# LPC2368_Breakout.net
KiCad netlist of a schematic drawn in EAGLE
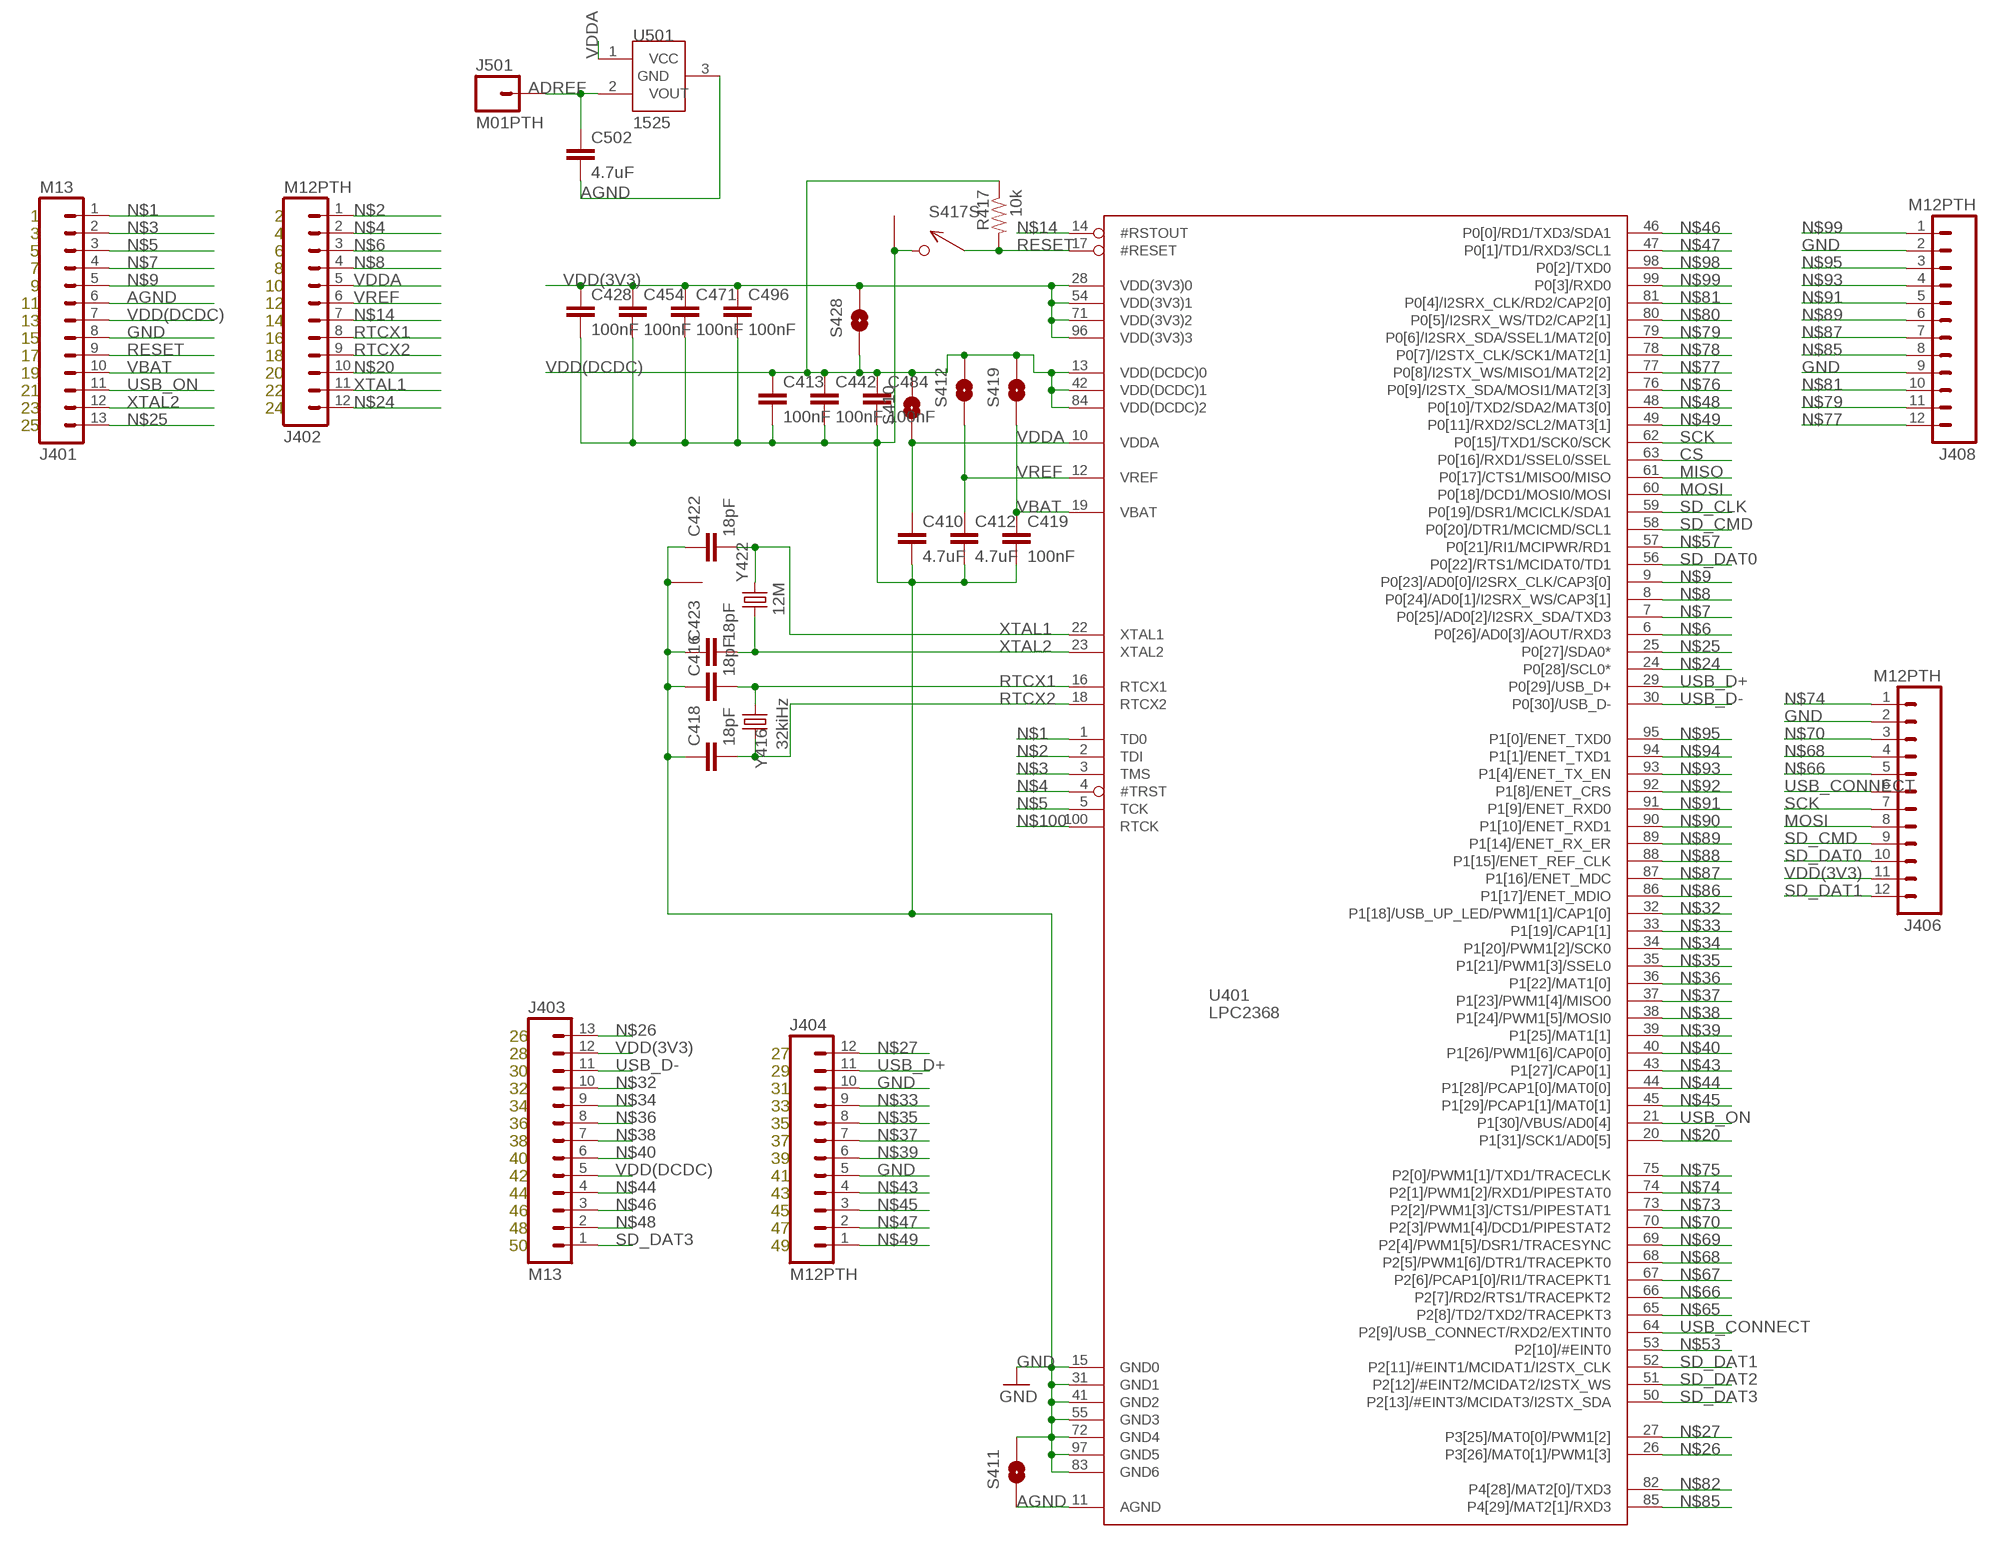
[diagram p0: schematic, sheet 1, part 1 of 2]
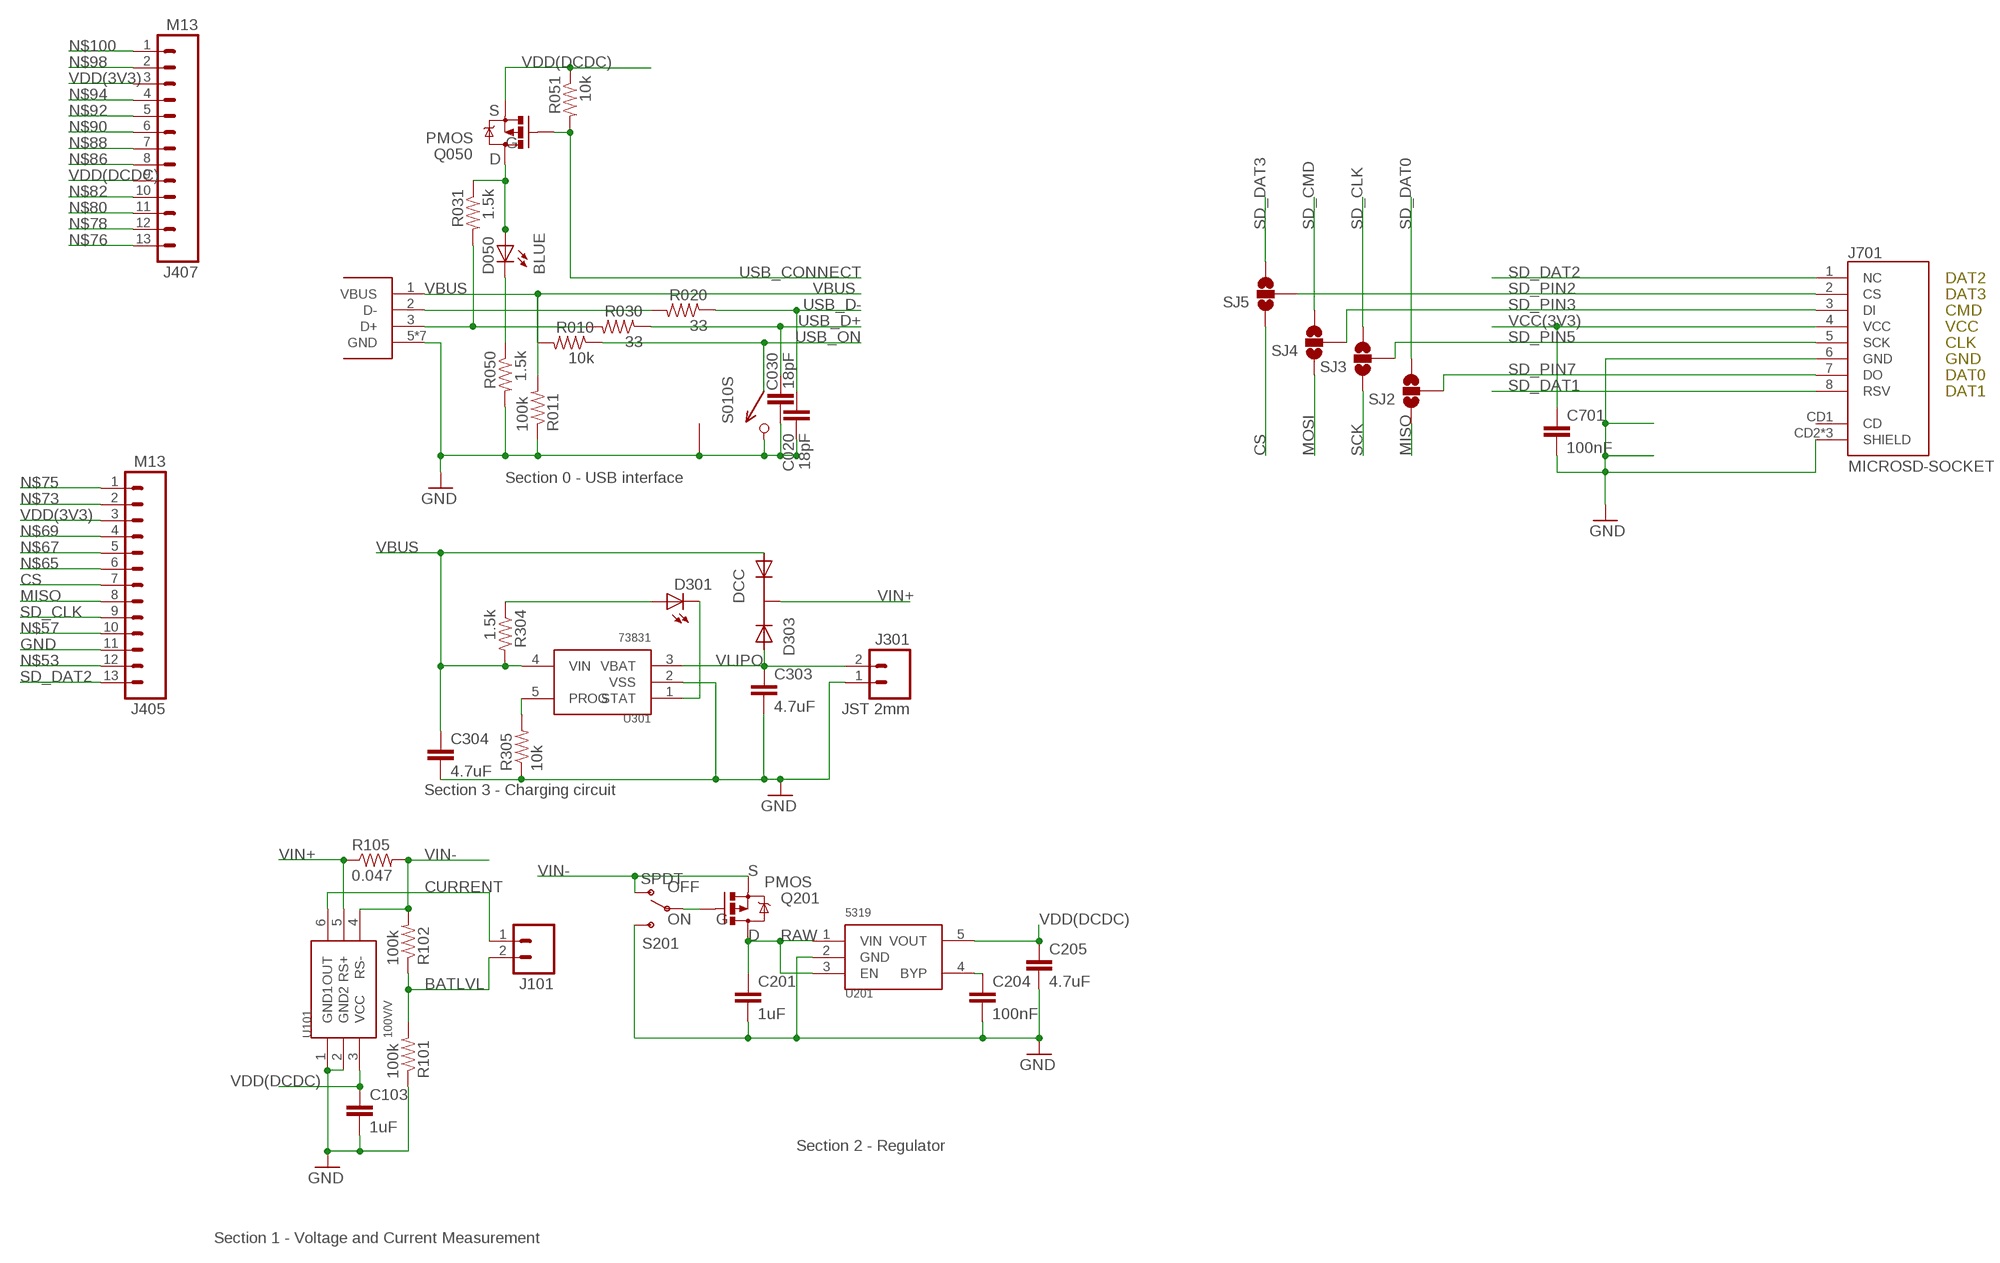
[diagram p1: schematic, sheet 1, part 2 of 2]

(export (version "E")
  (design (tool "Eeschema 10.0.6"))
  (components
    (comp (ref "C020")
      (value "18pF")
      (footprint "eagle-import:0402-CAP")
      (libsource (lib "eagle-import") (part "CAP0402-CAP"))
    )
    (comp (ref "C030")
      (value "18pF")
      (footprint "eagle-import:0402-CAP")
      (libsource (lib "eagle-import") (part "CAP0402-CAP"))
    )
    (comp (ref "C103")
      (value "1uF")
      (footprint "eagle-import:0402-CAP")
      (libsource (lib "eagle-import") (part "CAP0402-CAP"))
    )
    (comp (ref "C201")
      (value "1uF")
      (footprint "eagle-import:0402-CAP")
      (libsource (lib "eagle-import") (part "CAP0402-CAP"))
    )
    (comp (ref "C204")
      (value "100nF")
      (footprint "eagle-import:0402-CAP")
      (libsource (lib "eagle-import") (part "CAP0402-CAP"))
    )
    (comp (ref "C205")
      (value "4.7uF")
      (footprint "eagle-import:0402-CAP")
      (libsource (lib "eagle-import") (part "CAP0402-CAP"))
    )
    (comp (ref "C303")
      (value "4.7uF")
      (footprint "eagle-import:0402-CAP")
      (libsource (lib "eagle-import") (part "CAP0402-CAP"))
    )
    (comp (ref "C304")
      (value "4.7uF")
      (footprint "eagle-import:0402-CAP")
      (libsource (lib "eagle-import") (part "CAP0402-CAP"))
    )
    (comp (ref "C410")
      (value "4.7uF")
      (footprint "eagle-import:0402-CAP")
      (libsource (lib "eagle-import") (part "SparkFun-Passives_CAP0402-CAP"))
    )
    (comp (ref "C412")
      (value "4.7uF")
      (footprint "eagle-import:0402-CAP")
      (libsource (lib "eagle-import") (part "SparkFun-Passives_CAP0402-CAP"))
    )
    (comp (ref "C413")
      (value "100nF")
      (footprint "eagle-import:0402-CAP")
      (libsource (lib "eagle-import") (part "SparkFun-Passives_CAP0402-CAP"))
    )
    (comp (ref "C416")
      (value "18pF")
      (footprint "eagle-import:0402-CAP")
      (libsource (lib "eagle-import") (part "SparkFun-Passives_CAP0402-CAP"))
    )
    (comp (ref "C418")
      (value "18pF")
      (footprint "eagle-import:0402-CAP")
      (libsource (lib "eagle-import") (part "SparkFun-Passives_CAP0402-CAP"))
    )
    (comp (ref "C419")
      (value "100nF")
      (footprint "eagle-import:0402-CAP")
      (libsource (lib "eagle-import") (part "SparkFun-Passives_CAP0402-CAP"))
    )
    (comp (ref "C422")
      (value "18pF")
      (footprint "eagle-import:0402-CAP")
      (libsource (lib "eagle-import") (part "SparkFun-Passives_CAP0402-CAP"))
    )
    (comp (ref "C423")
      (value "18pF")
      (footprint "eagle-import:0402-CAP")
      (libsource (lib "eagle-import") (part "SparkFun-Passives_CAP0402-CAP"))
    )
    (comp (ref "C428")
      (value "100nF")
      (footprint "eagle-import:0402-CAP")
      (libsource (lib "eagle-import") (part "SparkFun-Passives_CAP0402-CAP"))
    )
    (comp (ref "C442")
      (value "100nF")
      (footprint "eagle-import:0402-CAP")
      (libsource (lib "eagle-import") (part "SparkFun-Passives_CAP0402-CAP"))
    )
    (comp (ref "C454")
      (value "100nF")
      (footprint "eagle-import:0402-CAP")
      (libsource (lib "eagle-import") (part "SparkFun-Passives_CAP0402-CAP"))
    )
    (comp (ref "C471")
      (value "100nF")
      (footprint "eagle-import:0402-CAP")
      (libsource (lib "eagle-import") (part "SparkFun-Passives_CAP0402-CAP"))
    )
    (comp (ref "C484")
      (value "100nF")
      (footprint "eagle-import:0402-CAP")
      (libsource (lib "eagle-import") (part "SparkFun-Passives_CAP0402-CAP"))
    )
    (comp (ref "C496")
      (value "100nF")
      (footprint "eagle-import:0402-CAP")
      (libsource (lib "eagle-import") (part "SparkFun-Passives_CAP0402-CAP"))
    )
    (comp (ref "C502")
      (value "4.7uF")
      (footprint "eagle-import:0402-CAP")
      (libsource (lib "eagle-import") (part "CAP0402-CAP"))
    )
    (comp (ref "C701")
      (value "100nF")
      (footprint "eagle-import:0402-CAP")
      (libsource (lib "eagle-import") (part "CAP0402-CAP"))
    )
    (comp (ref "D050")
      (value "BLUE")
      (footprint "eagle-import:LED-0603")
      (libsource (lib "eagle-import") (part "LED0603"))
    )
    (comp (ref "D301")
      (value "YELLOW")
      (footprint "eagle-import:LED-0603")
      (libsource (lib "eagle-import") (part "LED0603"))
    )
    (comp (ref "D303")
      (value "DCC")
      (footprint "eagle-import:SOT-23-3")
      (libsource (lib "eagle-import") (part "PMEG2005CT"))
    )
    (comp (ref "J001")
      (value "USB_MICROB_JST")
      (footprint "eagle-import:UB-MC5BR3-SD204-4S")
      (libsource (lib "eagle-import") (part "USB_MICROB_JST"))
    )
    (comp (ref "J101")
      (value "M02PTH")
      (footprint "eagle-import:1X02")
      (libsource (lib "eagle-import") (part "SparkFun-Connectors_M02PTH"))
    )
    (comp (ref "J301")
      (value "JST 2mm")
      (footprint "eagle-import:JST-2-SMD")
      (libsource (lib "eagle-import") (part "M02-JST-2MM-SMT"))
    )
    (comp (ref "J401")
      (value "M13")
      (footprint "eagle-import:1X13")
      (libsource (lib "eagle-import") (part "M13"))
    )
    (comp (ref "J402")
      (value "M12PTH")
      (footprint "eagle-import:1X12")
      (libsource (lib "eagle-import") (part "M12PTH"))
    )
    (comp (ref "J403")
      (value "M13")
      (footprint "eagle-import:1X13")
      (libsource (lib "eagle-import") (part "M13"))
    )
    (comp (ref "J404")
      (value "M12PTH")
      (footprint "eagle-import:1X12")
      (libsource (lib "eagle-import") (part "M12PTH"))
    )
    (comp (ref "J405")
      (value "M13")
      (footprint "eagle-import:1X13")
      (libsource (lib "eagle-import") (part "M13"))
    )
    (comp (ref "J406")
      (value "M12PTH")
      (footprint "eagle-import:1X12")
      (libsource (lib "eagle-import") (part "M12PTH"))
    )
    (comp (ref "J407")
      (value "M13")
      (footprint "eagle-import:1X13")
      (libsource (lib "eagle-import") (part "M13"))
    )
    (comp (ref "J408")
      (value "M12PTH")
      (footprint "eagle-import:1X12")
      (libsource (lib "eagle-import") (part "M12PTH"))
    )
    (comp (ref "J501")
      (value "M01PTH")
      (footprint "eagle-import:1X01")
      (libsource (lib "eagle-import") (part "M01PTH"))
    )
    (comp (ref "J701")
      (value "MICROSD-SOCKET")
      (footprint "eagle-import:MICROSD-SOCKET-PP")
      (libsource (lib "eagle-import") (part "MICROSD-SOCKET"))
    )
    (comp (ref "Q050")
      (value "PMOS")
      (footprint "eagle-import:SOT23-3")
      (libsource (lib "eagle-import") (part "MOSFET-PCHANNELSMD"))
    )
    (comp (ref "Q201")
      (value "PMOS")
      (footprint "eagle-import:SOT23-3")
      (libsource (lib "eagle-import") (part "MOSFET-PCHANNELSMD"))
    )
    (comp (ref "R010")
      (value "10k")
      (footprint "eagle-import:0402-RES")
      (libsource (lib "eagle-import") (part "RESISTOR0402-RES"))
    )
    (comp (ref "R011")
      (value "100k")
      (footprint "eagle-import:0402-RES")
      (libsource (lib "eagle-import") (part "RESISTOR0402-RES"))
    )
    (comp (ref "R020")
      (value "33")
      (footprint "eagle-import:0402-RES")
      (libsource (lib "eagle-import") (part "RESISTOR0402-RES"))
    )
    (comp (ref "R030")
      (value "33")
      (footprint "eagle-import:0402-RES")
      (libsource (lib "eagle-import") (part "RESISTOR0402-RES"))
    )
    (comp (ref "R031")
      (value "1.5k")
      (footprint "eagle-import:0402-RES")
      (libsource (lib "eagle-import") (part "RESISTOR0402-RES"))
    )
    (comp (ref "R050")
      (value "1.5k")
      (footprint "eagle-import:0402-RES")
      (libsource (lib "eagle-import") (part "RESISTOR0402-RES"))
    )
    (comp (ref "R051")
      (value "10k")
      (footprint "eagle-import:0402-RES")
      (libsource (lib "eagle-import") (part "RESISTOR0402-RES"))
    )
    (comp (ref "R101")
      (value "100k")
      (footprint "eagle-import:0402-RES")
      (libsource (lib "eagle-import") (part "RESISTOR0402-RES"))
    )
    (comp (ref "R102")
      (value "100k")
      (footprint "eagle-import:0402-RES")
      (libsource (lib "eagle-import") (part "RESISTOR0402-RES"))
    )
    (comp (ref "R105")
      (value "0.047")
      (footprint "eagle-import:0402-RES")
      (libsource (lib "eagle-import") (part "RESISTOR0402-RES"))
    )
    (comp (ref "R304")
      (value "1.5k")
      (footprint "eagle-import:0402-RES")
      (libsource (lib "eagle-import") (part "RESISTOR0402-RES"))
    )
    (comp (ref "R305")
      (value "10k")
      (footprint "eagle-import:0402-RES")
      (libsource (lib "eagle-import") (part "RESISTOR0402-RES"))
    )
    (comp (ref "R417")
      (value "10k")
      (footprint "eagle-import:0402-RES")
      (libsource (lib "eagle-import") (part "RESISTOR0402-RES"))
    )
    (comp (ref "S010")
      (value "SPST")
      (footprint "eagle-import:B3U-1100P")
      (fields (field (name "DIGIKEY") "SW1021CT-ND"))
      (libsource (lib "eagle-import") (part "B3U-1100P"))
    )
    (comp (ref "S201")
      (value "SPDT")
      (footprint "eagle-import:AYZ0202")
      (libsource (lib "eagle-import") (part "SWITCH-SPSTSMD"))
    )
    (comp (ref "S410")
      (value "SOLDERJUMPERNO")
      (footprint "eagle-import:SJ_2S-NO")
      (libsource (lib "eagle-import") (part "SOLDERJUMPERNO"))
    )
    (comp (ref "S411")
      (value "SOLDERJUMPERNO")
      (footprint "eagle-import:SJ_2S-NO")
      (libsource (lib "eagle-import") (part "SOLDERJUMPERNO"))
    )
    (comp (ref "S412")
      (value "SOLDERJUMPERNO")
      (footprint "eagle-import:SJ_2S-NO")
      (libsource (lib "eagle-import") (part "SOLDERJUMPERNO"))
    )
    (comp (ref "S417")
      (value "SPST")
      (footprint "eagle-import:B3U-1100P")
      (fields (field (name "DIGIKEY") "SW1021CT-ND"))
      (libsource (lib "eagle-import") (part "B3U-1100P"))
    )
    (comp (ref "S419")
      (value "SOLDERJUMPERNO")
      (footprint "eagle-import:SJ_2S-NO")
      (libsource (lib "eagle-import") (part "SOLDERJUMPERNO"))
    )
    (comp (ref "S428")
      (value "SOLDERJUMPERNO")
      (footprint "eagle-import:SJ_2S-NO")
      (libsource (lib "eagle-import") (part "SOLDERJUMPERNO"))
    )
    (comp (ref "SJ2")
      (value "SOLDERJUMPER_2WAYS")
      (footprint "eagle-import:SJ_3")
      (libsource (lib "eagle-import") (part "SOLDERJUMPER_2WAYS"))
    )
    (comp (ref "SJ3")
      (value "SOLDERJUMPER_2WAYS")
      (footprint "eagle-import:SJ_3")
      (libsource (lib "eagle-import") (part "SOLDERJUMPER_2WAYS"))
    )
    (comp (ref "SJ4")
      (value "SOLDERJUMPER_2WAYS")
      (footprint "eagle-import:SJ_3")
      (libsource (lib "eagle-import") (part "SOLDERJUMPER_2WAYS"))
    )
    (comp (ref "SJ5")
      (value "SOLDERJUMPER_2WAYS")
      (footprint "eagle-import:SJ_3")
      (libsource (lib "eagle-import") (part "SOLDERJUMPER_2WAYS"))
    )
    (comp (ref "U101")
      (value "100V/V")
      (footprint "eagle-import:SOT-23-6")
      (libsource (lib "eagle-import") (part "MAX4173"))
    )
    (comp (ref "U201")
      (value "5319")
      (footprint "eagle-import:SOT-23-5")
      (libsource (lib "eagle-import") (part "MIC5319D5"))
    )
    (comp (ref "U301")
      (value "73831")
      (footprint "eagle-import:SOT-23-5")
      (libsource (lib "eagle-import") (part "MCP73831"))
    )
    (comp (ref "U401")
      (value "LPC2368")
      (footprint "eagle-import:LQFP100")
      (libsource (lib "eagle-import") (part "LPC2368"))
    )
    (comp (ref "U501")
      (value "1525")
      (footprint "eagle-import:SOT-23-3")
      (libsource (lib "eagle-import") (part "MCP1525"))
    )
    (comp (ref "Y416")
      (value "32kiHz")
      (footprint "eagle-import:CRYSTAL-32KHZ-SMD")
      (libsource (lib "eagle-import") (part "CRYSTAL32-SMD"))
    )
    (comp (ref "Y422")
      (value "12M")
      (footprint "eagle-import:CRYSTAL_SMD")
      (fields (field (name "DIGIKEY") "887-1316-1-ND"))
      (libsource (lib "eagle-import") (part "TSX-3225"))
    )
  )
  (nets
    (net (code "1") (name "/ADREF") (class "Default")
      (node (ref "C502") (pin "1") (pinfunction "1_1") (pintype "passive"))
      (node (ref "J501") (pin "1") (pinfunction "1_1") (pintype "passive"))
      (node (ref "U501") (pin "2") (pinfunction "VOUT_2") (pintype "bidirectional"))
    )
    (net (code "2") (name "/AGND") (class "Default")
      (node (ref "C502") (pin "2") (pinfunction "2_2") (pintype "passive"))
      (node (ref "J401") (pin "6") (pinfunction "6_6") (pintype "passive"))
      (node (ref "S411") (pin "1") (pinfunction "1_1") (pintype "passive"))
      (node (ref "U401") (pin "11") (pinfunction "AGND_11") (pintype "bidirectional"))
      (node (ref "U501") (pin "3") (pinfunction "GND_3") (pintype "bidirectional"))
    )
    (net (code "3") (name "/BATLVL") (class "Default")
      (node (ref "J101") (pin "2") (pinfunction "2_2") (pintype "passive"))
      (node (ref "R101") (pin "2") (pinfunction "2_2") (pintype "passive"))
      (node (ref "R102") (pin "1") (pinfunction "1_1") (pintype "passive"))
    )
    (net (code "4") (name "/CS") (class "Default")
      (node (ref "J405") (pin "7") (pinfunction "7_7") (pintype "passive"))
      (node (ref "SJ5") (pin "1") (pinfunction "1_1") (pintype "passive"))
      (node (ref "U401") (pin "63") (pinfunction "P0[16]/RXD1/SSEL0/SSEL_63") (pintype "bidirectional"))
    )
    (net (code "5") (name "/CURRENT") (class "Default")
      (node (ref "J101") (pin "1") (pinfunction "1_1") (pintype "passive"))
      (node (ref "U101") (pin "6") (pinfunction "OUT_6") (pintype "bidirectional"))
    )
    (net (code "6") (name "/MISO") (class "Default")
      (node (ref "J405") (pin "8") (pinfunction "8_8") (pintype "passive"))
      (node (ref "SJ2") (pin "1") (pinfunction "1_1") (pintype "passive"))
      (node (ref "U401") (pin "61") (pinfunction "P0[17]/CTS1/MISO0/MISO_61") (pintype "bidirectional"))
    )
    (net (code "7") (name "/MOSI") (class "Default")
      (node (ref "J406") (pin "8") (pinfunction "8_8") (pintype "passive"))
      (node (ref "SJ4") (pin "1") (pinfunction "1_1") (pintype "passive"))
      (node (ref "U401") (pin "60") (pinfunction "P0[18]/DCD1/MOSI0/MOSI_60") (pintype "bidirectional"))
    )
    (net (code "8") (name "/N$1") (class "Default")
      (node (ref "J401") (pin "1") (pinfunction "1_1") (pintype "passive"))
      (node (ref "U401") (pin "1") (pinfunction "TD0_1") (pintype "bidirectional"))
    )
    (net (code "9") (name "/N$2") (class "Default")
      (node (ref "J402") (pin "1") (pinfunction "1_1") (pintype "passive"))
      (node (ref "U401") (pin "2") (pinfunction "TDI_2") (pintype "bidirectional"))
    )
    (net (code "10") (name "/N$3") (class "Default")
      (node (ref "J401") (pin "2") (pinfunction "2_2") (pintype "passive"))
      (node (ref "U401") (pin "3") (pinfunction "TMS_3") (pintype "bidirectional"))
    )
    (net (code "11") (name "/N$4") (class "Default")
      (node (ref "J402") (pin "2") (pinfunction "2_2") (pintype "passive"))
      (node (ref "U401") (pin "4") (pinfunction "#TRST_4") (pintype "bidirectional"))
    )
    (net (code "12") (name "/N$5") (class "Default")
      (node (ref "J401") (pin "3") (pinfunction "3_3") (pintype "passive"))
      (node (ref "U401") (pin "5") (pinfunction "TCK_5") (pintype "bidirectional"))
    )
    (net (code "13") (name "/N$6") (class "Default")
      (node (ref "J402") (pin "3") (pinfunction "3_3") (pintype "passive"))
      (node (ref "U401") (pin "6") (pinfunction "P0[26]/AD0[3]/AOUT/RXD3_6") (pintype "bidirectional"))
    )
    (net (code "14") (name "/N$7") (class "Default")
      (node (ref "J401") (pin "4") (pinfunction "4_4") (pintype "passive"))
      (node (ref "U401") (pin "7") (pinfunction "P0[25]/AD0[2]/I2SRX_SDA/TXD3_7") (pintype "bidirectional"))
    )
    (net (code "15") (name "/N$8") (class "Default")
      (node (ref "J402") (pin "4") (pinfunction "4_4") (pintype "passive"))
      (node (ref "U401") (pin "8") (pinfunction "P0[24]/AD0[1]/I2SRX_WS/CAP3[1]_8") (pintype "bidirectional"))
    )
    (net (code "16") (name "/N$9") (class "Default")
      (node (ref "J401") (pin "5") (pinfunction "5_5") (pintype "passive"))
      (node (ref "U401") (pin "9") (pinfunction "P0[23]/AD0[0]/I2SRX_CLK/CAP3[0]_9") (pintype "bidirectional"))
    )
    (net (code "17") (name "/N$14") (class "Default")
      (node (ref "J402") (pin "7") (pinfunction "7_7") (pintype "passive"))
      (node (ref "U401") (pin "14") (pinfunction "#RSTOUT_14") (pintype "bidirectional"))
    )
    (net (code "18") (name "/N$20") (class "Default")
      (node (ref "J402") (pin "10") (pinfunction "10_10") (pintype "passive"))
      (node (ref "U401") (pin "20") (pinfunction "P1[31]/SCK1/AD0[5]_20") (pintype "bidirectional"))
    )
    (net (code "19") (name "/N$24") (class "Default")
      (node (ref "J402") (pin "12") (pinfunction "12_12") (pintype "passive"))
      (node (ref "U401") (pin "24") (pinfunction "P0[28]/SCL0*_24") (pintype "bidirectional"))
    )
    (net (code "20") (name "/N$25") (class "Default")
      (node (ref "J401") (pin "13") (pinfunction "13_13") (pintype "passive"))
      (node (ref "U401") (pin "25") (pinfunction "P0[27]/SDA0*_25") (pintype "bidirectional"))
    )
    (net (code "21") (name "/N$26") (class "Default")
      (node (ref "J403") (pin "13") (pinfunction "13_13") (pintype "passive"))
      (node (ref "U401") (pin "26") (pinfunction "P3[26]/MAT0[1]/PWM1[3]_26") (pintype "bidirectional"))
    )
    (net (code "22") (name "/N$27") (class "Default")
      (node (ref "J404") (pin "12") (pinfunction "12_12") (pintype "passive"))
      (node (ref "U401") (pin "27") (pinfunction "P3[25]/MAT0[0]/PWM1[2]_27") (pintype "bidirectional"))
    )
    (net (code "23") (name "/N$32") (class "Default")
      (node (ref "J403") (pin "10") (pinfunction "10_10") (pintype "passive"))
      (node (ref "U401") (pin "32") (pinfunction "P1[18]/USB_UP_LED/PWM1[1]/CAP1[0]_32") (pintype "bidirectional"))
    )
    (net (code "24") (name "/N$33") (class "Default")
      (node (ref "J404") (pin "9") (pinfunction "9_9") (pintype "passive"))
      (node (ref "U401") (pin "33") (pinfunction "P1[19]/CAP1[1]_33") (pintype "bidirectional"))
    )
    (net (code "25") (name "/N$34") (class "Default")
      (node (ref "J403") (pin "9") (pinfunction "9_9") (pintype "passive"))
      (node (ref "U401") (pin "34") (pinfunction "P1[20]/PWM1[2]/SCK0_34") (pintype "bidirectional"))
    )
    (net (code "26") (name "/N$35") (class "Default")
      (node (ref "J404") (pin "8") (pinfunction "8_8") (pintype "passive"))
      (node (ref "U401") (pin "35") (pinfunction "P1[21]/PWM1[3]/SSEL0_35") (pintype "bidirectional"))
    )
    (net (code "27") (name "/N$36") (class "Default")
      (node (ref "J403") (pin "8") (pinfunction "8_8") (pintype "passive"))
      (node (ref "U401") (pin "36") (pinfunction "P1[22]/MAT1[0]_36") (pintype "bidirectional"))
    )
    (net (code "28") (name "/N$37") (class "Default")
      (node (ref "J404") (pin "7") (pinfunction "7_7") (pintype "passive"))
      (node (ref "U401") (pin "37") (pinfunction "P1[23]/PWM1[4]/MISO0_37") (pintype "bidirectional"))
    )
    (net (code "29") (name "/N$38") (class "Default")
      (node (ref "J403") (pin "7") (pinfunction "7_7") (pintype "passive"))
      (node (ref "U401") (pin "38") (pinfunction "P1[24]/PWM1[5]/MOSI0_38") (pintype "bidirectional"))
    )
    (net (code "30") (name "/N$39") (class "Default")
      (node (ref "J404") (pin "6") (pinfunction "6_6") (pintype "passive"))
      (node (ref "U401") (pin "39") (pinfunction "P1[25]/MAT1[1]_39") (pintype "bidirectional"))
    )
    (net (code "31") (name "/N$40") (class "Default")
      (node (ref "J403") (pin "6") (pinfunction "6_6") (pintype "passive"))
      (node (ref "U401") (pin "40") (pinfunction "P1[26]/PWM1[6]/CAP0[0]_40") (pintype "bidirectional"))
    )
    (net (code "32") (name "/N$43") (class "Default")
      (node (ref "J404") (pin "4") (pinfunction "4_4") (pintype "passive"))
      (node (ref "U401") (pin "43") (pinfunction "P1[27]/CAP0[1]_43") (pintype "bidirectional"))
    )
    (net (code "33") (name "/N$44") (class "Default")
      (node (ref "J403") (pin "4") (pinfunction "4_4") (pintype "passive"))
      (node (ref "U401") (pin "44") (pinfunction "P1[28]/PCAP1[0]/MAT0[0]_44") (pintype "bidirectional"))
    )
    (net (code "34") (name "/N$45") (class "Default")
      (node (ref "J404") (pin "3") (pinfunction "3_3") (pintype "passive"))
      (node (ref "U401") (pin "45") (pinfunction "P1[29]/PCAP1[1]/MAT0[1]_45") (pintype "bidirectional"))
    )
    (net (code "35") (name "/N$46") (class "Default")
      (node (ref "J403") (pin "3") (pinfunction "3_3") (pintype "passive"))
      (node (ref "U401") (pin "46") (pinfunction "P0[0]/RD1/TXD3/SDA1_46") (pintype "bidirectional"))
    )
    (net (code "36") (name "/N$47") (class "Default")
      (node (ref "J404") (pin "2") (pinfunction "2_2") (pintype "passive"))
      (node (ref "U401") (pin "47") (pinfunction "P0[1]/TD1/RXD3/SCL1_47") (pintype "bidirectional"))
    )
    (net (code "37") (name "/N$48") (class "Default")
      (node (ref "J403") (pin "2") (pinfunction "2_2") (pintype "passive"))
      (node (ref "U401") (pin "48") (pinfunction "P0[10]/TXD2/SDA2/MAT3[0]_48") (pintype "bidirectional"))
    )
    (net (code "38") (name "/N$49") (class "Default")
      (node (ref "J404") (pin "1") (pinfunction "1_1") (pintype "passive"))
      (node (ref "U401") (pin "49") (pinfunction "P0[11]/RXD2/SCL2/MAT3[1]_49") (pintype "bidirectional"))
    )
    (net (code "39") (name "/N$53") (class "Default")
      (node (ref "J405") (pin "12") (pinfunction "12_12") (pintype "passive"))
      (node (ref "U401") (pin "53") (pinfunction "P2[10]/#EINT0_53") (pintype "bidirectional"))
    )
    (net (code "40") (name "/N$57") (class "Default")
      (node (ref "J405") (pin "10") (pinfunction "10_10") (pintype "passive"))
      (node (ref "U401") (pin "57") (pinfunction "P0[21]/RI1/MCIPWR/RD1_57") (pintype "bidirectional"))
    )
    (net (code "41") (name "/N$65") (class "Default")
      (node (ref "J405") (pin "6") (pinfunction "6_6") (pintype "passive"))
      (node (ref "U401") (pin "65") (pinfunction "P2[8]/TD2/TXD2/TRACEPKT3_65") (pintype "bidirectional"))
    )
    (net (code "42") (name "/N$66") (class "Default")
      (node (ref "J406") (pin "5") (pinfunction "5_5") (pintype "passive"))
      (node (ref "U401") (pin "66") (pinfunction "P2[7]/RD2/RTS1/TRACEPKT2_66") (pintype "bidirectional"))
    )
    (net (code "43") (name "/N$67") (class "Default")
      (node (ref "J405") (pin "5") (pinfunction "5_5") (pintype "passive"))
      (node (ref "U401") (pin "67") (pinfunction "P2[6]/PCAP1[0]/RI1/TRACEPKT1_67") (pintype "bidirectional"))
    )
    (net (code "44") (name "/N$68") (class "Default")
      (node (ref "J406") (pin "4") (pinfunction "4_4") (pintype "passive"))
      (node (ref "U401") (pin "68") (pinfunction "P2[5]/PWM1[6]/DTR1/TRACEPKT0_68") (pintype "bidirectional"))
    )
    (net (code "45") (name "/N$69") (class "Default")
      (node (ref "J405") (pin "4") (pinfunction "4_4") (pintype "passive"))
      (node (ref "U401") (pin "69") (pinfunction "P2[4]/PWM1[5]/DSR1/TRACESYNC_69") (pintype "bidirectional"))
    )
    (net (code "46") (name "/N$70") (class "Default")
      (node (ref "J406") (pin "3") (pinfunction "3_3") (pintype "passive"))
      (node (ref "U401") (pin "70") (pinfunction "P2[3]/PWM1[4]/DCD1/PIPESTAT2_70") (pintype "bidirectional"))
    )
    (net (code "47") (name "/N$73") (class "Default")
      (node (ref "J405") (pin "2") (pinfunction "2_2") (pintype "passive"))
      (node (ref "U401") (pin "73") (pinfunction "P2[2]/PWM1[3]/CTS1/PIPESTAT1_73") (pintype "bidirectional"))
    )
    (net (code "48") (name "/N$74") (class "Default")
      (node (ref "J406") (pin "1") (pinfunction "1_1") (pintype "passive"))
      (node (ref "U401") (pin "74") (pinfunction "P2[1]/PWM1[2]/RXD1/PIPESTAT0_74") (pintype "bidirectional"))
    )
    (net (code "49") (name "/N$75") (class "Default")
      (node (ref "J405") (pin "1") (pinfunction "1_1") (pintype "passive"))
      (node (ref "U401") (pin "75") (pinfunction "P2[0]/PWM1[1]/TXD1/TRACECLK_75") (pintype "bidirectional"))
    )
    (net (code "50") (name "/N$76") (class "Default")
      (node (ref "J407") (pin "13") (pinfunction "13_13") (pintype "passive"))
      (node (ref "U401") (pin "76") (pinfunction "P0[9]/I2STX_SDA/MOSI1/MAT2[3]_76") (pintype "bidirectional"))
    )
    (net (code "51") (name "/N$77") (class "Default")
      (node (ref "J408") (pin "12") (pinfunction "12_12") (pintype "passive"))
      (node (ref "U401") (pin "77") (pinfunction "P0[8]/I2STX_WS/MISO1/MAT2[2]_77") (pintype "bidirectional"))
    )
    (net (code "52") (name "/N$78") (class "Default")
      (node (ref "J407") (pin "12") (pinfunction "12_12") (pintype "passive"))
      (node (ref "U401") (pin "78") (pinfunction "P0[7]/I2STX_CLK/SCK1/MAT2[1]_78") (pintype "bidirectional"))
    )
    (net (code "53") (name "/N$79") (class "Default")
      (node (ref "J408") (pin "11") (pinfunction "11_11") (pintype "passive"))
      (node (ref "U401") (pin "79") (pinfunction "P0[6]/I2SRX_SDA/SSEL1/MAT2[0]_79") (pintype "bidirectional"))
    )
    (net (code "54") (name "/N$80") (class "Default")
      (node (ref "J407") (pin "11") (pinfunction "11_11") (pintype "passive"))
      (node (ref "U401") (pin "80") (pinfunction "P0[5]/I2SRX_WS/TD2/CAP2[1]_80") (pintype "bidirectional"))
    )
    (net (code "55") (name "/N$81") (class "Default")
      (node (ref "J408") (pin "10") (pinfunction "10_10") (pintype "passive"))
      (node (ref "U401") (pin "81") (pinfunction "P0[4]/I2SRX_CLK/RD2/CAP2[0]_81") (pintype "bidirectional"))
    )
    (net (code "56") (name "/N$82") (class "Default")
      (node (ref "J407") (pin "10") (pinfunction "10_10") (pintype "passive"))
      (node (ref "U401") (pin "82") (pinfunction "P4[28]/MAT2[0]/TXD3_82") (pintype "bidirectional"))
    )
    (net (code "57") (name "/N$85") (class "Default")
      (node (ref "J408") (pin "8") (pinfunction "8_8") (pintype "passive"))
      (node (ref "U401") (pin "85") (pinfunction "P4[29]/MAT2[1]/RXD3_85") (pintype "bidirectional"))
    )
    (net (code "58") (name "/N$86") (class "Default")
      (node (ref "J407") (pin "8") (pinfunction "8_8") (pintype "passive"))
      (node (ref "U401") (pin "86") (pinfunction "P1[17]/ENET_MDIO_86") (pintype "bidirectional"))
    )
    (net (code "59") (name "/N$87") (class "Default")
      (node (ref "J408") (pin "7") (pinfunction "7_7") (pintype "passive"))
      (node (ref "U401") (pin "87") (pinfunction "P1[16]/ENET_MDC_87") (pintype "bidirectional"))
    )
    (net (code "60") (name "/N$88") (class "Default")
      (node (ref "J407") (pin "7") (pinfunction "7_7") (pintype "passive"))
      (node (ref "U401") (pin "88") (pinfunction "P1[15]/ENET_REF_CLK_88") (pintype "bidirectional"))
    )
    (net (code "61") (name "/N$89") (class "Default")
      (node (ref "J408") (pin "6") (pinfunction "6_6") (pintype "passive"))
      (node (ref "U401") (pin "89") (pinfunction "P1[14]/ENET_RX_ER_89") (pintype "bidirectional"))
    )
    (net (code "62") (name "/N$90") (class "Default")
      (node (ref "J407") (pin "6") (pinfunction "6_6") (pintype "passive"))
      (node (ref "U401") (pin "90") (pinfunction "P1[10]/ENET_RXD1_90") (pintype "bidirectional"))
    )
    (net (code "63") (name "/N$91") (class "Default")
      (node (ref "J408") (pin "5") (pinfunction "5_5") (pintype "passive"))
      (node (ref "U401") (pin "91") (pinfunction "P1[9]/ENET_RXD0_91") (pintype "bidirectional"))
    )
    (net (code "64") (name "/N$92") (class "Default")
      (node (ref "J407") (pin "5") (pinfunction "5_5") (pintype "passive"))
      (node (ref "U401") (pin "92") (pinfunction "P1[8]/ENET_CRS_92") (pintype "bidirectional"))
    )
    (net (code "65") (name "/N$93") (class "Default")
      (node (ref "J408") (pin "4") (pinfunction "4_4") (pintype "passive"))
      (node (ref "U401") (pin "93") (pinfunction "P1[4]/ENET_TX_EN_93") (pintype "bidirectional"))
    )
    (net (code "66") (name "/N$94") (class "Default")
      (node (ref "J407") (pin "4") (pinfunction "4_4") (pintype "passive"))
      (node (ref "U401") (pin "94") (pinfunction "P1[1]/ENET_TXD1_94") (pintype "bidirectional"))
    )
    (net (code "67") (name "/N$95") (class "Default")
      (node (ref "J408") (pin "3") (pinfunction "3_3") (pintype "passive"))
      (node (ref "U401") (pin "95") (pinfunction "P1[0]/ENET_TXD0_95") (pintype "bidirectional"))
    )
    (net (code "68") (name "/N$98") (class "Default")
      (node (ref "J407") (pin "2") (pinfunction "2_2") (pintype "passive"))
      (node (ref "U401") (pin "98") (pinfunction "P0[2]/TXD0_98") (pintype "bidirectional"))
    )
    (net (code "69") (name "/N$99") (class "Default")
      (node (ref "J408") (pin "1") (pinfunction "1_1") (pintype "passive"))
      (node (ref "U401") (pin "99") (pinfunction "P0[3]/RXD0_99") (pintype "bidirectional"))
    )
    (net (code "70") (name "/N$100") (class "Default")
      (node (ref "J407") (pin "1") (pinfunction "1_1") (pintype "passive"))
      (node (ref "U401") (pin "100") (pinfunction "RTCK_100") (pintype "bidirectional"))
    )
    (net (code "71") (name "/RAW") (class "Default")
      (node (ref "C201") (pin "1") (pinfunction "1_1") (pintype "passive"))
      (node (ref "Q201") (pin "3") (pinfunction "D_3") (pintype "passive"))
      (node (ref "U201") (pin "1") (pinfunction "VIN_1") (pintype "bidirectional"))
      (node (ref "U201") (pin "3") (pinfunction "EN_3") (pintype "bidirectional"))
    )
    (net (code "72") (name "/RESET") (class "Default")
      (node (ref "J401") (pin "9") (pinfunction "9_9") (pintype "passive"))
      (node (ref "R417") (pin "2") (pinfunction "2_2") (pintype "passive"))
      (node (ref "S417") (pin "P$1") (pinfunction "1_P$1") (pintype "bidirectional"))
      (node (ref "U401") (pin "17") (pinfunction "#RESET_17") (pintype "bidirectional"))
    )
    (net (code "73") (name "/RTCX1") (class "Default")
      (node (ref "C416") (pin "2") (pinfunction "2_2") (pintype "passive"))
      (node (ref "J402") (pin "8") (pinfunction "8_8") (pintype "passive"))
      (node (ref "U401") (pin "16") (pinfunction "RTCX1_16") (pintype "bidirectional"))
      (node (ref "Y416") (pin "X1") (pinfunction "1_X1") (pintype "passive"))
    )
    (net (code "74") (name "/RTCX2") (class "Default")
      (node (ref "C418") (pin "2") (pinfunction "2_2") (pintype "passive"))
      (node (ref "J402") (pin "9") (pinfunction "9_9") (pintype "passive"))
      (node (ref "U401") (pin "18") (pinfunction "RTCX2_18") (pintype "bidirectional"))
      (node (ref "Y416") (pin "X2") (pinfunction "2_X2") (pintype "passive"))
    )
    (net (code "75") (name "/SCK") (class "Default")
      (node (ref "J406") (pin "7") (pinfunction "7_7") (pintype "passive"))
      (node (ref "SJ3") (pin "1") (pinfunction "1_1") (pintype "passive"))
      (node (ref "U401") (pin "62") (pinfunction "P0[15]/TXD1/SCK0/SCK_62") (pintype "bidirectional"))
    )
    (net (code "76") (name "/SD_CLK") (class "Default")
      (node (ref "J405") (pin "9") (pinfunction "9_9") (pintype "passive"))
      (node (ref "SJ3") (pin "3") (pinfunction "3_3") (pintype "passive"))
      (node (ref "U401") (pin "59") (pinfunction "P0[19]/DSR1/MCICLK/SDA1_59") (pintype "bidirectional"))
    )
    (net (code "77") (name "/SD_CMD") (class "Default")
      (node (ref "J406") (pin "9") (pinfunction "9_9") (pintype "passive"))
      (node (ref "SJ4") (pin "3") (pinfunction "3_3") (pintype "passive"))
      (node (ref "U401") (pin "58") (pinfunction "P0[20]/DTR1/MCICMD/SCL1_58") (pintype "bidirectional"))
    )
    (net (code "78") (name "/SD_DAT0") (class "Default")
      (node (ref "J406") (pin "10") (pinfunction "10_10") (pintype "passive"))
      (node (ref "SJ2") (pin "3") (pinfunction "3_3") (pintype "passive"))
      (node (ref "U401") (pin "56") (pinfunction "P0[22]/RTS1/MCIDAT0/TD1_56") (pintype "bidirectional"))
    )
    (net (code "79") (name "/SD_DAT1") (class "Default")
      (node (ref "J406") (pin "12") (pinfunction "12_12") (pintype "passive"))
      (node (ref "J701") (pin "8") (pinfunction "RSV_8") (pintype "bidirectional"))
      (node (ref "U401") (pin "52") (pinfunction "P2[11]/#EINT1/MCIDAT1/I2STX_CLK_52") (pintype "bidirectional"))
    )
    (net (code "80") (name "/SD_DAT2") (class "Default")
      (node (ref "J405") (pin "13") (pinfunction "13_13") (pintype "passive"))
      (node (ref "J701") (pin "1") (pinfunction "NC_1") (pintype "bidirectional"))
      (node (ref "U401") (pin "51") (pinfunction "P2[12]/#EINT2/MCIDAT2/I2STX_WS_51") (pintype "bidirectional"))
    )
    (net (code "81") (name "/SD_DAT3") (class "Default")
      (node (ref "J403") (pin "1") (pinfunction "1_1") (pintype "passive"))
      (node (ref "SJ5") (pin "3") (pinfunction "3_3") (pintype "passive"))
      (node (ref "U401") (pin "50") (pinfunction "P2[13]/#EINT3/MCIDAT3/I2STX_SDA_50") (pintype "bidirectional"))
    )
    (net (code "82") (name "/SD_PIN2") (class "Default")
      (node (ref "J701") (pin "2") (pinfunction "CS_2") (pintype "bidirectional"))
      (node (ref "SJ5") (pin "2") (pinfunction "2_2") (pintype "passive"))
    )
    (net (code "83") (name "/SD_PIN3") (class "Default")
      (node (ref "J701") (pin "3") (pinfunction "DI_3") (pintype "bidirectional"))
      (node (ref "SJ4") (pin "2") (pinfunction "2_2") (pintype "passive"))
    )
    (net (code "84") (name "/SD_PIN5") (class "Default")
      (node (ref "J701") (pin "5") (pinfunction "SCK_5") (pintype "bidirectional"))
      (node (ref "SJ3") (pin "2") (pinfunction "2_2") (pintype "passive"))
    )
    (net (code "85") (name "/SD_PIN7") (class "Default")
      (node (ref "J701") (pin "7") (pinfunction "DO_7") (pintype "bidirectional"))
      (node (ref "SJ2") (pin "2") (pinfunction "2_2") (pintype "passive"))
    )
    (net (code "86") (name "/USB_CONNECT") (class "Default")
      (node (ref "J406") (pin "6") (pinfunction "6_6") (pintype "passive"))
      (node (ref "Q050") (pin "1") (pinfunction "G_1") (pintype "passive"))
      (node (ref "R051") (pin "2") (pinfunction "2_2") (pintype "passive"))
      (node (ref "U401") (pin "64") (pinfunction "P2[9]/USB_CONNECT/RXD2/EXTINT0_64") (pintype "bidirectional"))
    )
    (net (code "87") (name "/USB_D+") (class "Default")
      (node (ref "C030") (pin "1") (pinfunction "1_1") (pintype "passive"))
      (node (ref "J404") (pin "11") (pinfunction "11_11") (pintype "passive"))
      (node (ref "R030") (pin "1") (pinfunction "1_1") (pintype "passive"))
      (node (ref "U401") (pin "29") (pinfunction "P0[29]/USB_D+_29") (pintype "bidirectional"))
    )
    (net (code "88") (name "/USB_D-") (class "Default")
      (node (ref "C020") (pin "1") (pinfunction "1_1") (pintype "passive"))
      (node (ref "J403") (pin "11") (pinfunction "11_11") (pintype "passive"))
      (node (ref "R020") (pin "1") (pinfunction "1_1") (pintype "passive"))
      (node (ref "U401") (pin "30") (pinfunction "P0[30]/USB_D-_30") (pintype "bidirectional"))
    )
    (net (code "89") (name "/USB_ON") (class "Default")
      (node (ref "J401") (pin "11") (pinfunction "11_11") (pintype "passive"))
      (node (ref "R010") (pin "1") (pinfunction "1_1") (pintype "passive"))
      (node (ref "S010") (pin "P$1") (pinfunction "1_P$1") (pintype "bidirectional"))
      (node (ref "U401") (pin "21") (pinfunction "P1[30]/VBUS/AD0[4]_21") (pintype "bidirectional"))
    )
    (net (code "90") (name "/VBAT") (class "Default")
      (node (ref "C419") (pin "1") (pinfunction "1_1") (pintype "passive"))
      (node (ref "J401") (pin "10") (pinfunction "10_10") (pintype "passive"))
      (node (ref "S419") (pin "1") (pinfunction "1_1") (pintype "passive"))
      (node (ref "U401") (pin "19") (pinfunction "VBAT_19") (pintype "bidirectional"))
    )
    (net (code "91") (name "/VBUS") (class "Default")
      (node (ref "C304") (pin "1") (pinfunction "1_1") (pintype "passive"))
      (node (ref "D303") (pin "1") (pinfunction "A1_1") (pintype "passive"))
      (node (ref "J001") (pin "1") (pinfunction "VBUS_1") (pintype "bidirectional"))
      (node (ref "R010") (pin "2") (pinfunction "2_2") (pintype "passive"))
      (node (ref "R011") (pin "2") (pinfunction "2_2") (pintype "passive"))
      (node (ref "R304") (pin "2") (pinfunction "2_2") (pintype "passive"))
      (node (ref "U301") (pin "4") (pinfunction "VIN_4") (pintype "bidirectional"))
    )
    (net (code "92") (name "/VCC(3V3)") (class "Default")
      (node (ref "C701") (pin "1") (pinfunction "1_1") (pintype "passive"))
      (node (ref "J701") (pin "4") (pinfunction "VCC_4") (pintype "bidirectional"))
    )
    (net (code "93") (name "/VDD(3V3)") (class "Default")
      (node (ref "C428") (pin "1") (pinfunction "1_1") (pintype "passive"))
      (node (ref "C454") (pin "1") (pinfunction "1_1") (pintype "passive"))
      (node (ref "C471") (pin "1") (pinfunction "1_1") (pintype "passive"))
      (node (ref "C496") (pin "1") (pinfunction "1_1") (pintype "passive"))
      (node (ref "J403") (pin "12") (pinfunction "12_12") (pintype "passive"))
      (node (ref "J405") (pin "3") (pinfunction "3_3") (pintype "passive"))
      (node (ref "J406") (pin "11") (pinfunction "11_11") (pintype "passive"))
      (node (ref "J407") (pin "3") (pinfunction "3_3") (pintype "passive"))
      (node (ref "S428") (pin "2") (pinfunction "2_2") (pintype "passive"))
      (node (ref "U401") (pin "28") (pinfunction "VDD(3V3)0_28") (pintype "bidirectional"))
      (node (ref "U401") (pin "54") (pinfunction "VDD(3V3)1_54") (pintype "bidirectional"))
      (node (ref "U401") (pin "71") (pinfunction "VDD(3V3)2_71") (pintype "bidirectional"))
      (node (ref "U401") (pin "96") (pinfunction "VDD(3V3)3_96") (pintype "bidirectional"))
    )
    (net (code "94") (name "/VDD(DCDC)") (class "Default")
      (node (ref "C103") (pin "1") (pinfunction "1_1") (pintype "passive"))
      (node (ref "C205") (pin "1") (pinfunction "1_1") (pintype "passive"))
      (node (ref "C413") (pin "1") (pinfunction "1_1") (pintype "passive"))
      (node (ref "C442") (pin "1") (pinfunction "1_1") (pintype "passive"))
      (node (ref "C484") (pin "1") (pinfunction "1_1") (pintype "passive"))
      (node (ref "J401") (pin "7") (pinfunction "7_7") (pintype "passive"))
      (node (ref "J403") (pin "5") (pinfunction "5_5") (pintype "passive"))
      (node (ref "J407") (pin "9") (pinfunction "9_9") (pintype "passive"))
      (node (ref "Q050") (pin "2") (pinfunction "S_2") (pintype "passive"))
      (node (ref "R051") (pin "1") (pinfunction "1_1") (pintype "passive"))
      (node (ref "R417") (pin "1") (pinfunction "1_1") (pintype "passive"))
      (node (ref "S410") (pin "2") (pinfunction "2_2") (pintype "passive"))
      (node (ref "S412") (pin "2") (pinfunction "2_2") (pintype "passive"))
      (node (ref "S419") (pin "2") (pinfunction "2_2") (pintype "passive"))
      (node (ref "S428") (pin "1") (pinfunction "1_1") (pintype "passive"))
      (node (ref "U101") (pin "3") (pinfunction "VCC_3") (pintype "bidirectional"))
      (node (ref "U201") (pin "5") (pinfunction "VOUT_5") (pintype "bidirectional"))
      (node (ref "U401") (pin "13") (pinfunction "VDD(DCDC)0_13") (pintype "bidirectional"))
      (node (ref "U401") (pin "42") (pinfunction "VDD(DCDC)1_42") (pintype "bidirectional"))
      (node (ref "U401") (pin "84") (pinfunction "VDD(DCDC)2_84") (pintype "bidirectional"))
    )
    (net (code "95") (name "/VDDA") (class "Default")
      (node (ref "C410") (pin "1") (pinfunction "1_1") (pintype "passive"))
      (node (ref "J402") (pin "5") (pinfunction "5_5") (pintype "passive"))
      (node (ref "S410") (pin "1") (pinfunction "1_1") (pintype "passive"))
      (node (ref "U401") (pin "10") (pinfunction "VDDA_10") (pintype "bidirectional"))
      (node (ref "U501") (pin "1") (pinfunction "VCC_1") (pintype "bidirectional"))
    )
    (net (code "96") (name "/VIN+") (class "Default")
      (node (ref "D303") (pin "3") (pinfunction "K_3") (pintype "passive"))
      (node (ref "R105") (pin "1") (pinfunction "1_1") (pintype "passive"))
      (node (ref "U101") (pin "5") (pinfunction "RS+_5") (pintype "bidirectional"))
    )
    (net (code "97") (name "/VIN-") (class "Default")
      (node (ref "Q201") (pin "2") (pinfunction "S_2") (pintype "passive"))
      (node (ref "R102") (pin "2") (pinfunction "2_2") (pintype "passive"))
      (node (ref "R105") (pin "2") (pinfunction "2_2") (pintype "passive"))
      (node (ref "S201") (pin "1") (pinfunction "O_1") (pintype "passive"))
      (node (ref "U101") (pin "4") (pinfunction "RS-_4") (pintype "bidirectional"))
    )
    (net (code "98") (name "/VLIPO") (class "Default")
      (node (ref "C303") (pin "1") (pinfunction "1_1") (pintype "passive"))
      (node (ref "D303") (pin "2") (pinfunction "A2_2") (pintype "passive"))
      (node (ref "J301") (pin "2") (pinfunction "2_2") (pintype "passive"))
      (node (ref "U301") (pin "3") (pinfunction "VBAT_3") (pintype "bidirectional"))
    )
    (net (code "99") (name "/VREF") (class "Default")
      (node (ref "C412") (pin "1") (pinfunction "1_1") (pintype "passive"))
      (node (ref "J402") (pin "6") (pinfunction "6_6") (pintype "passive"))
      (node (ref "S412") (pin "1") (pinfunction "1_1") (pintype "passive"))
      (node (ref "U401") (pin "12") (pinfunction "VREF_12") (pintype "bidirectional"))
    )
    (net (code "100") (name "/XTAL1") (class "Default")
      (node (ref "C422") (pin "2") (pinfunction "2_2") (pintype "passive"))
      (node (ref "J402") (pin "11") (pinfunction "11_11") (pintype "passive"))
      (node (ref "U401") (pin "22") (pinfunction "XTAL1_22") (pintype "bidirectional"))
      (node (ref "Y422") (pin "3") (pinfunction "2_3") (pintype "passive"))
    )
    (net (code "101") (name "/XTAL2") (class "Default")
      (node (ref "C423") (pin "2") (pinfunction "2_2") (pintype "passive"))
      (node (ref "J401") (pin "12") (pinfunction "12_12") (pintype "passive"))
      (node (ref "U401") (pin "23") (pinfunction "XTAL2_23") (pintype "bidirectional"))
      (node (ref "Y422") (pin "1") (pinfunction "1_1") (pintype "passive"))
    )
    (net (code "102") (name "GND") (class "Default")
      (node (ref "C020") (pin "2") (pinfunction "2_2") (pintype "passive"))
      (node (ref "C030") (pin "2") (pinfunction "2_2") (pintype "passive"))
      (node (ref "C103") (pin "2") (pinfunction "2_2") (pintype "passive"))
      (node (ref "C201") (pin "2") (pinfunction "2_2") (pintype "passive"))
      (node (ref "C204") (pin "2") (pinfunction "2_2") (pintype "passive"))
      (node (ref "C205") (pin "2") (pinfunction "2_2") (pintype "passive"))
      (node (ref "C303") (pin "2") (pinfunction "2_2") (pintype "passive"))
      (node (ref "C304") (pin "2") (pinfunction "2_2") (pintype "passive"))
      (node (ref "C410") (pin "2") (pinfunction "2_2") (pintype "passive"))
      (node (ref "C412") (pin "2") (pinfunction "2_2") (pintype "passive"))
      (node (ref "C413") (pin "2") (pinfunction "2_2") (pintype "passive"))
      (node (ref "C416") (pin "1") (pinfunction "1_1") (pintype "passive"))
      (node (ref "C418") (pin "1") (pinfunction "1_1") (pintype "passive"))
      (node (ref "C419") (pin "2") (pinfunction "2_2") (pintype "passive"))
      (node (ref "C422") (pin "1") (pinfunction "1_1") (pintype "passive"))
      (node (ref "C423") (pin "1") (pinfunction "1_1") (pintype "passive"))
      (node (ref "C428") (pin "2") (pinfunction "2_2") (pintype "passive"))
      (node (ref "C442") (pin "2") (pinfunction "2_2") (pintype "passive"))
      (node (ref "C454") (pin "2") (pinfunction "2_2") (pintype "passive"))
      (node (ref "C471") (pin "2") (pinfunction "2_2") (pintype "passive"))
      (node (ref "C484") (pin "2") (pinfunction "2_2") (pintype "passive"))
      (node (ref "C496") (pin "2") (pinfunction "2_2") (pintype "passive"))
      (node (ref "C701") (pin "2") (pinfunction "2_2") (pintype "passive"))
      (node (ref "J001") (pin "5") (pinfunction "GND_5") (pintype "bidirectional"))
      (node (ref "J001") (pin "P$10") (pinfunction "GND_P$10") (pintype "bidirectional"))
      (node (ref "J001") (pin "P$11") (pinfunction "GND_P$11") (pintype "bidirectional"))
      (node (ref "J001") (pin "P$6") (pinfunction "GND_P$6") (pintype "bidirectional"))
      (node (ref "J001") (pin "P$7") (pinfunction "GND_P$7") (pintype "bidirectional"))
      (node (ref "J001") (pin "P$8") (pinfunction "GND_P$8") (pintype "bidirectional"))
      (node (ref "J001") (pin "P$9") (pinfunction "GND_P$9") (pintype "bidirectional"))
      (node (ref "J301") (pin "1") (pinfunction "1_1") (pintype "passive"))
      (node (ref "J401") (pin "8") (pinfunction "8_8") (pintype "passive"))
      (node (ref "J404") (pin "10") (pinfunction "10_10") (pintype "passive"))
      (node (ref "J404") (pin "5") (pinfunction "5_5") (pintype "passive"))
      (node (ref "J405") (pin "11") (pinfunction "11_11") (pintype "passive"))
      (node (ref "J406") (pin "2") (pinfunction "2_2") (pintype "passive"))
      (node (ref "J408") (pin "2") (pinfunction "2_2") (pintype "passive"))
      (node (ref "J408") (pin "9") (pinfunction "9_9") (pintype "passive"))
      (node (ref "J701") (pin "6") (pinfunction "GND_6") (pintype "bidirectional"))
      (node (ref "J701") (pin "CD2") (pinfunction "SHIELD_CD2") (pintype "bidirectional"))
      (node (ref "J701") (pin "GND1") (pinfunction "SHIELD_GND1") (pintype "bidirectional"))
      (node (ref "J701") (pin "GND3") (pinfunction "SHIELD_GND3") (pintype "bidirectional"))
      (node (ref "R011") (pin "1") (pinfunction "1_1") (pintype "passive"))
      (node (ref "R050") (pin "2") (pinfunction "2_2") (pintype "passive"))
      (node (ref "R101") (pin "1") (pinfunction "1_1") (pintype "passive"))
      (node (ref "R305") (pin "1") (pinfunction "1_1") (pintype "passive"))
      (node (ref "S010") (pin "P$2") (pinfunction "2_P$2") (pintype "bidirectional"))
      (node (ref "S010") (pin "P$3") (pinfunction "1_P$3") (pintype "bidirectional"))
      (node (ref "S201") (pin "3") (pinfunction "S_3") (pintype "passive"))
      (node (ref "S411") (pin "2") (pinfunction "2_2") (pintype "passive"))
      (node (ref "S417") (pin "P$2") (pinfunction "2_P$2") (pintype "bidirectional"))
      (node (ref "S417") (pin "P$3") (pinfunction "1_P$3") (pintype "bidirectional"))
      (node (ref "U101") (pin "1") (pinfunction "GND1_1") (pintype "bidirectional"))
      (node (ref "U101") (pin "2") (pinfunction "GND2_2") (pintype "bidirectional"))
      (node (ref "U201") (pin "2") (pinfunction "GND_2") (pintype "bidirectional"))
      (node (ref "U301") (pin "2") (pinfunction "VSS_2") (pintype "bidirectional"))
      (node (ref "U401") (pin "15") (pinfunction "GND0_15") (pintype "bidirectional"))
      (node (ref "U401") (pin "31") (pinfunction "GND1_31") (pintype "bidirectional"))
      (node (ref "U401") (pin "41") (pinfunction "GND2_41") (pintype "bidirectional"))
      (node (ref "U401") (pin "55") (pinfunction "GND3_55") (pintype "bidirectional"))
      (node (ref "U401") (pin "72") (pinfunction "GND4_72") (pintype "bidirectional"))
      (node (ref "U401") (pin "83") (pinfunction "GND6_83") (pintype "bidirectional"))
      (node (ref "U401") (pin "97") (pinfunction "GND5_97") (pintype "bidirectional"))
      (node (ref "Y422") (pin "2") (pinfunction "1_2") (pintype "bidirectional"))
      (node (ref "Y422") (pin "4") (pinfunction "1_4") (pintype "bidirectional"))
    )
    (net (code "103") (name "Net-(D050-PadC)") (class "Default")
      (node (ref "D050") (pin "C") (pinfunction "C_C") (pintype "passive"))
      (node (ref "R050") (pin "1") (pinfunction "1_1") (pintype "passive"))
    )
    (net (code "104") (name "Net-(D301-PadA)") (class "Default")
      (node (ref "D301") (pin "A") (pinfunction "A_A") (pintype "passive"))
      (node (ref "R304") (pin "1") (pinfunction "1_1") (pintype "passive"))
    )
    (net (code "105") (name "Net-(J001-D+)") (class "Default")
      (node (ref "J001") (pin "3") (pinfunction "D+_3") (pintype "bidirectional"))
      (node (ref "R030") (pin "2") (pinfunction "2_2") (pintype "passive"))
      (node (ref "R031") (pin "2") (pinfunction "2_2") (pintype "passive"))
    )
    (net (code "106") (name "Net-(J001-D-)") (class "Default")
      (node (ref "J001") (pin "2") (pinfunction "D-_2") (pintype "bidirectional"))
      (node (ref "R020") (pin "2") (pinfunction "2_2") (pintype "passive"))
    )
    (net (code "107") (name "Net-(Q050-D)") (class "Default")
      (node (ref "D050") (pin "A") (pinfunction "A_A") (pintype "passive"))
      (node (ref "Q050") (pin "3") (pinfunction "D_3") (pintype "passive"))
      (node (ref "R031") (pin "1") (pinfunction "1_1") (pintype "passive"))
    )
    (net (code "108") (name "Net-(Q201-G)") (class "Default")
      (node (ref "Q201") (pin "1") (pinfunction "G_1") (pintype "passive"))
      (node (ref "S201") (pin "2") (pinfunction "P_2") (pintype "passive"))
    )
    (net (code "109") (name "Net-(U201-BYP)") (class "Default")
      (node (ref "C204") (pin "1") (pinfunction "1_1") (pintype "passive"))
      (node (ref "U201") (pin "4") (pinfunction "BYP_4") (pintype "bidirectional"))
    )
    (net (code "110") (name "Net-(U301-PROG)") (class "Default")
      (node (ref "R305") (pin "2") (pinfunction "2_2") (pintype "passive"))
      (node (ref "U301") (pin "5") (pinfunction "PROG_5") (pintype "bidirectional"))
    )
    (net (code "111") (name "Net-(U301-STAT)") (class "Default")
      (node (ref "D301") (pin "C") (pinfunction "C_C") (pintype "passive"))
      (node (ref "U301") (pin "1") (pinfunction "STAT_1") (pintype "bidirectional"))
    )
    (net (code "112") (name "unconnected-(J701-CD-PadCD1)") (class "Default")
      (node (ref "J701") (pin "CD1") (pinfunction "CD_CD1") (pintype "bidirectional"))
    )
  )
)
